# Sheet1.net
KiCad netlist of a schematic drawn in Altium Designer
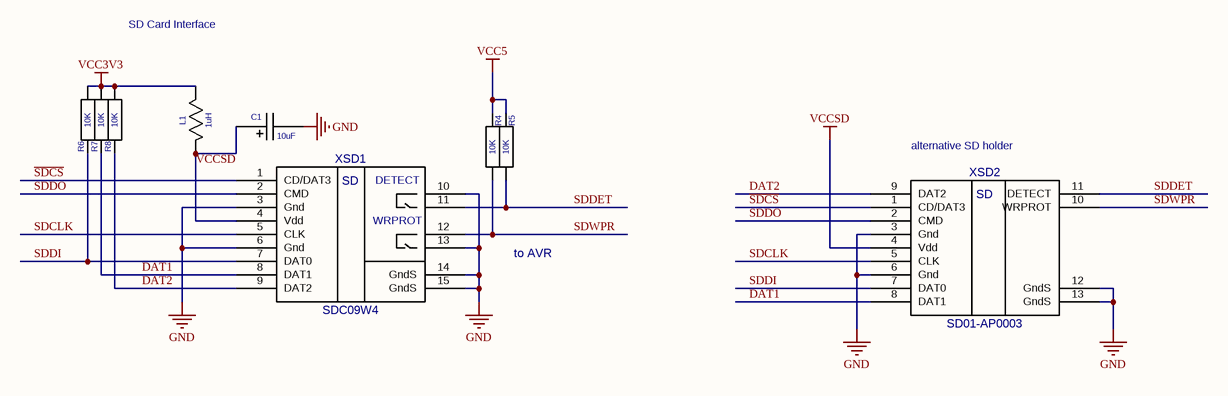
[diagram p0: Sheet1.SCHDOC]

(export (version "E")
  (design (tool "Eeschema 10.0.6"))
  (components
    (comp (ref "C1")
      (value "10uF")
      (footprint "EC-CHIP")
      (description "ECAPCHIP")
      (libsource (lib "*") (part "ECAPCHIP"))
    )
    (comp (ref "L1")
      (value "1uH")
      (footprint "L-CHIP")
      (description "L-CHIP")
      (libsource (lib "*") (part "L-CHIP"))
    )
    (comp (ref "R4")
      (value "10K")
      (footprint "R-CHIP")
      (description "RESCHIP")
      (libsource (lib "*") (part "RESCHIP"))
    )
    (comp (ref "R5")
      (value "10K")
      (footprint "R-CHIP")
      (description "RESCHIP")
      (libsource (lib "*") (part "RESCHIP"))
    )
    (comp (ref "R6")
      (value "10K")
      (footprint "R-CHIP")
      (description "RESCHIP")
      (libsource (lib "*") (part "RESCHIP"))
    )
    (comp (ref "R7")
      (value "10K")
      (footprint "R-CHIP")
      (description "RESCHIP")
      (libsource (lib "*") (part "RESCHIP"))
    )
    (comp (ref "R8")
      (value "10K")
      (footprint "R-CHIP")
      (description "RESCHIP")
      (libsource (lib "*") (part "RESCHIP"))
    )
    (comp (ref "XSD1") (value "SDC09W4") (footprint "SDC09W4") (libsource (lib "*") (part "SDC09W4")))
    (comp (ref "XSD2")
      (value "SD01-AP0003")
      (footprint "SD01-AP0003")
      (libsource (lib "*") (part "SD01-AP0003"))
    )
  )
  (nets
    (net (code "1") (name "/DAT1") (class "Default")
      (node (ref "R7") (pin "2") (pinfunction "i/o1_2") (pintype "passive"))
      (node (ref "XSD1") (pin "8") (pinfunction "DAT1_8") (pintype "passive"))
      (node (ref "XSD2") (pin "8") (pinfunction "DAT1_8") (pintype "passive"))
    )
    (net (code "2") (name "/DAT2") (class "Default")
      (node (ref "R8") (pin "2") (pinfunction "i/o1_2") (pintype "passive"))
      (node (ref "XSD1") (pin "9") (pinfunction "DAT2_9") (pintype "passive"))
      (node (ref "XSD2") (pin "9") (pinfunction "DAT2_9") (pintype "passive"))
    )
    (net (code "3") (name "/SDCLK") (class "Default")
      (node (ref "XSD1") (pin "5") (pinfunction "CLK_5") (pintype "passive"))
      (node (ref "XSD2") (pin "5") (pinfunction "CLK_5") (pintype "passive"))
    )
    (net (code "4") (name "/SDDET") (class "Default")
      (node (ref "R5") (pin "1") (pinfunction "i/o_1") (pintype "passive"))
      (node (ref "XSD1") (pin "11") (pinfunction "DETECT_11") (pintype "passive"))
      (node (ref "XSD2") (pin "11") (pinfunction "DETECT_11") (pintype "passive"))
    )
    (net (code "5") (name "/SDDI") (class "Default")
      (node (ref "R6") (pin "2") (pinfunction "i/o1_2") (pintype "passive"))
      (node (ref "XSD1") (pin "7") (pinfunction "DAT0_7") (pintype "passive"))
      (node (ref "XSD2") (pin "7") (pinfunction "DAT0_7") (pintype "passive"))
    )
    (net (code "6") (name "/SDDO") (class "Default")
      (node (ref "XSD1") (pin "2") (pinfunction "CMD_2") (pintype "passive"))
      (node (ref "XSD2") (pin "2") (pinfunction "CMD_2") (pintype "passive"))
    )
    (net (code "7") (name "/SDWPR") (class "Default")
      (node (ref "R4") (pin "1") (pinfunction "i/o_1") (pintype "passive"))
      (node (ref "XSD1") (pin "12") (pinfunction "WRPROT_12") (pintype "passive"))
      (node (ref "XSD2") (pin "10") (pinfunction "WRPROT_10") (pintype "passive"))
    )
    (net (code "8") (name "/~{SDCS}") (class "Default")
      (node (ref "XSD1") (pin "1") (pinfunction "CD/DAT3_1") (pintype "passive"))
      (node (ref "XSD2") (pin "1") (pinfunction "CD/DAT3_1") (pintype "passive"))
    )
    (net (code "9") (name "GND") (class "Default")
      (node (ref "C1") (pin "2") (pintype "passive"))
      (node (ref "XSD1") (pin "10") (pinfunction "DETECT_10") (pintype "passive"))
      (node (ref "XSD1") (pin "13") (pinfunction "WRPROT_13") (pintype "passive"))
      (node (ref "XSD1") (pin "14") (pinfunction "GndS_14") (pintype "passive"))
      (node (ref "XSD1") (pin "15") (pinfunction "GndS_15") (pintype "passive"))
      (node (ref "XSD1") (pin "3") (pinfunction "Gnd_3") (pintype "passive"))
      (node (ref "XSD1") (pin "6") (pinfunction "Gnd_6") (pintype "passive"))
      (node (ref "XSD2") (pin "12") (pinfunction "GndS_12") (pintype "passive"))
      (node (ref "XSD2") (pin "13") (pinfunction "GndS_13") (pintype "passive"))
      (node (ref "XSD2") (pin "3") (pinfunction "Gnd_3") (pintype "passive"))
      (node (ref "XSD2") (pin "6") (pinfunction "Gnd_6") (pintype "passive"))
    )
    (net (code "10") (name "VCC3V3") (class "Default")
      (node (ref "L1") (pin "1") (pintype "passive"))
      (node (ref "R6") (pin "1") (pinfunction "i/o_1") (pintype "passive"))
      (node (ref "R7") (pin "1") (pinfunction "i/o_1") (pintype "passive"))
      (node (ref "R8") (pin "1") (pinfunction "i/o_1") (pintype "passive"))
    )
    (net (code "11") (name "VCC5") (class "Default")
      (node (ref "R4") (pin "2") (pinfunction "i/o1_2") (pintype "passive"))
      (node (ref "R5") (pin "2") (pinfunction "i/o1_2") (pintype "passive"))
    )
    (net (code "12") (name "VCCSD") (class "Default")
      (node (ref "C1") (pin "1") (pintype "passive"))
      (node (ref "L1") (pin "2") (pintype "passive"))
      (node (ref "XSD1") (pin "4") (pinfunction "Vdd_4") (pintype "passive"))
      (node (ref "XSD2") (pin "4") (pinfunction "Vdd_4") (pintype "passive"))
    )
    (net (code "13") (name "unconnected-(XSD2-Pad14)") (class "Default")
      (node (ref "XSD2") (pin "14") (pintype "passive"))
    )
    (net (code "14") (name "unconnected-(XSD2-Pad15)") (class "Default")
      (node (ref "XSD2") (pin "15") (pintype "passive"))
    )
  )
)
